# Interfaces.net
KiCad netlist of a schematic drawn in Altium Designer
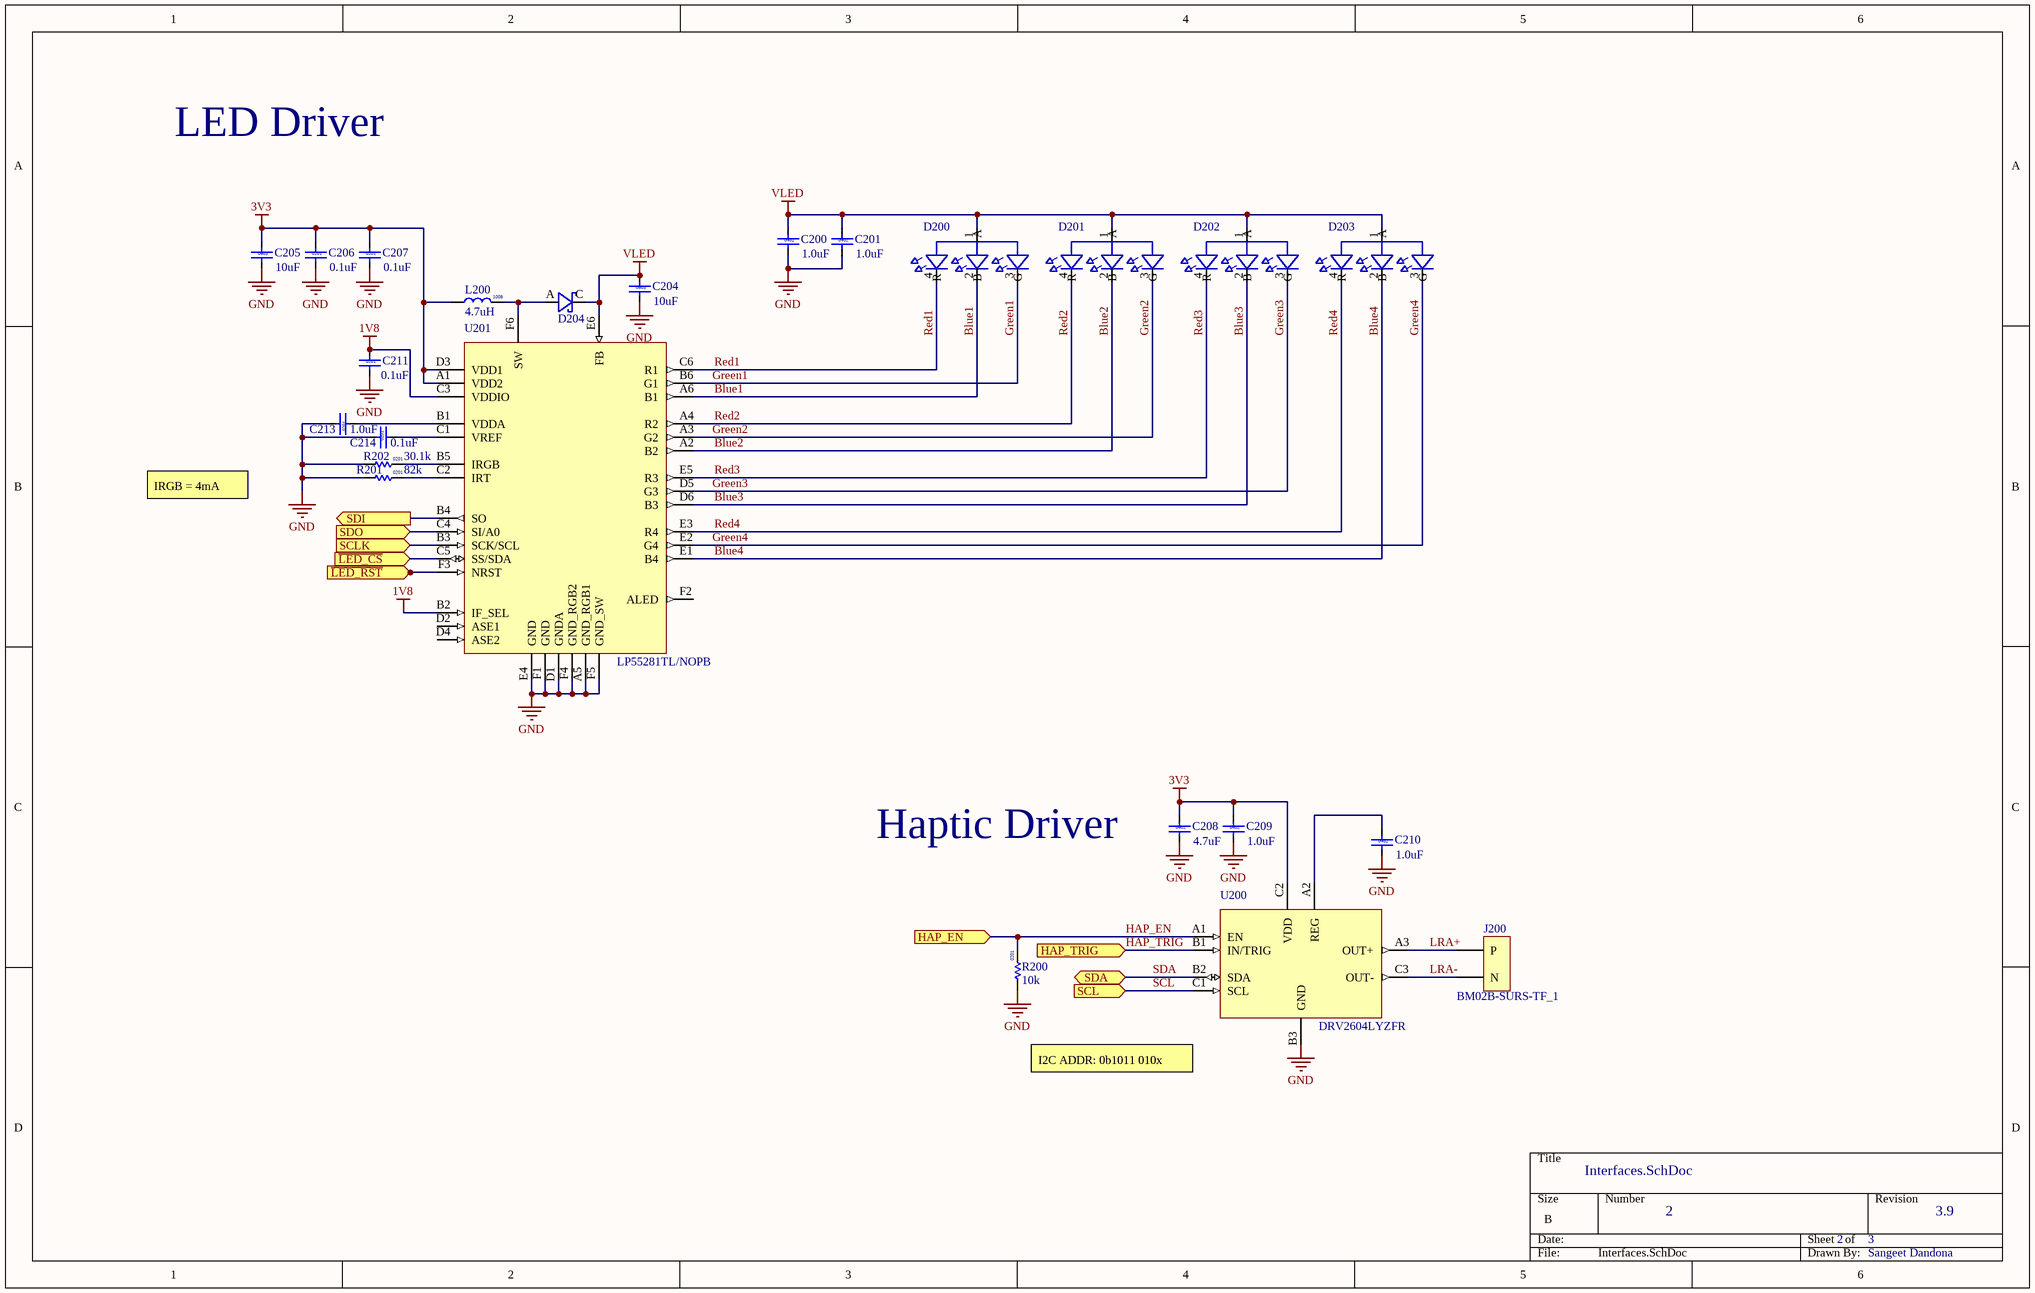
[diagram p0: Interfaces.SchDoc]

(export (version "E")
  (design (tool "Eeschema 10.0.6"))
  (components
    (comp (ref "C200")
      (value "1.0uF")
      (footprint "Cap 0402 HD")
      (description "CAP CER 1UF 10V 10% X5R 0402")
      (fields (field (name "SIZE") "0402") (field (name "MF") "Murata Electronics North America"))
      (libsource (lib "Rigado_AltiumLib") (part "Cap Chip"))
    )
    (comp (ref "C201")
      (value "1.0uF")
      (footprint "Cap 0402 HD")
      (description "CAP CER 1UF 10V 10% X5R 0402")
      (fields (field (name "SIZE") "0402") (field (name "MF") "Murata Electronics North America"))
      (libsource (lib "Rigado_AltiumLib") (part "Cap Chip"))
    )
    (comp (ref "C204")
      (value "10uF")
      (footprint "Cap 0603")
      (description "CAP CER 10UF 10V 20% X5R 0603")
      (fields (field (name "SIZE") "0603") (field (name "MF") "TDK Corporation"))
      (libsource (lib "Rigado_AltiumLib") (part "Cap Chip"))
    )
    (comp (ref "C205")
      (value "10uF")
      (footprint "Cap 0603")
      (description "CAP CER 10UF 10V 20% X5R 0603")
      (fields (field (name "SIZE") "0603") (field (name "MF") "TDK Corporation"))
      (libsource (lib "Rigado_AltiumLib") (part "Cap Chip"))
    )
    (comp (ref "C206")
      (value "0.1uF")
      (footprint "Cap 0201 HD")
      (description "CAP CER 0.1UF 6.3V 10% X5R 0201")
      (fields (field (name "SIZE") "0201") (field (name "MF") "Murata Electronics North America"))
      (libsource (lib "Rigado_AltiumLib") (part "Cap Chip"))
    )
    (comp (ref "C207")
      (value "0.1uF")
      (footprint "Cap 0201 HD")
      (description "CAP CER 0.1UF 6.3V 10% X5R 0201")
      (fields (field (name "SIZE") "0201") (field (name "MF") "Murata Electronics North America"))
      (libsource (lib "Rigado_AltiumLib") (part "Cap Chip"))
    )
    (comp (ref "C208")
      (value "4.7uF")
      (footprint "Cap 0402 HD")
      (description "CAP CER 4.7UF 10V 20% X5R 0402")
      (fields (field (name "SIZE") "0402") (field (name "MF") "Samsung Electro-Mechanics America, Inc."))
      (libsource (lib "Rigado_AltiumLib") (part "Cap Chip"))
    )
    (comp (ref "C209")
      (value "1.0uF")
      (footprint "Cap 0402 HD")
      (description "CAP CER 1UF 10V 10% X5R 0402")
      (fields (field (name "SIZE") "0402") (field (name "MF") "Murata Electronics North America"))
      (libsource (lib "Rigado_AltiumLib") (part "Cap Chip"))
    )
    (comp (ref "C210")
      (value "1.0uF")
      (footprint "Cap 0402 HD")
      (description "CAP CER 1UF 10V 10% X5R 0402")
      (fields (field (name "SIZE") "0402") (field (name "MF") "Murata Electronics North America"))
      (libsource (lib "Rigado_AltiumLib") (part "Cap Chip"))
    )
    (comp (ref "C211")
      (value "0.1uF")
      (footprint "Cap 0201 HD")
      (description "CAP CER 0.1UF 6.3V 10% X5R 0201")
      (fields (field (name "SIZE") "0201") (field (name "MF") "Murata Electronics North America"))
      (libsource (lib "Rigado_AltiumLib") (part "Cap Chip"))
    )
    (comp (ref "C213")
      (value "1.0uF")
      (footprint "Cap 0201 HD")
      (description "CAP CER 1UF 6.3V 20% X5R 0201")
      (fields (field (name "SIZE") "0201") (field (name "MF") "Samsung Electro-Mechanics America, Inc."))
      (libsource (lib "Rigado_AltiumLib") (part "Cap Chip"))
    )
    (comp (ref "C214")
      (value "0.1uF")
      (footprint "Cap 0201 HD")
      (description "CAP CER 0.1UF 6.3V 10% X5R 0201")
      (fields (field (name "SIZE") "0201") (field (name "MF") "Murata Electronics North America"))
      (libsource (lib "Rigado_AltiumLib") (part "Cap Chip"))
    )
    (comp (ref "D200")
      (value "~")
      (footprint "4-PLCC")
      (description "LED RGB 3-IN-1 SMD 4PLCC")
      (fields (field (name "MF") "Cree Inc."))
      (libsource (lib "Rigado_AltiumLib") (part "LED_RGB_CA_2"))
    )
    (comp (ref "D201")
      (value "~")
      (footprint "4-PLCC")
      (description "LED RGB 3-IN-1 SMD 4PLCC")
      (fields (field (name "MF") "Cree Inc."))
      (libsource (lib "Rigado_AltiumLib") (part "LED_RGB_CA_2"))
    )
    (comp (ref "D202")
      (value "~")
      (footprint "4-PLCC")
      (description "LED RGB 3-IN-1 SMD 4PLCC")
      (fields (field (name "MF") "Cree Inc."))
      (libsource (lib "Rigado_AltiumLib") (part "LED_RGB_CA_2"))
    )
    (comp (ref "D203")
      (value "~")
      (footprint "4-PLCC")
      (description "LED RGB 3-IN-1 SMD 4PLCC")
      (fields (field (name "MF") "Cree Inc."))
      (libsource (lib "Rigado_AltiumLib") (part "LED_RGB_CA_2"))
    )
    (comp (ref "D204")
      (value "~")
      (footprint "SOD-123F_U")
      (description "DIODE SCHOTTKY 20V 1A SOD123FL")
      (fields (field (name "MF") "ON Semiconductor"))
      (libsource (lib "LOCAL_Rigado_AltiumLib") (part "Diode_Schottky"))
    )
    (comp (ref "J200")
      (value "BM02B-SURS-TF_1")
      (footprint "BM02B-SURS-TF")
      (description "CONN HDR SUR TOP 2POS 0.8MM TIN")
      (fields (field (name "MF") "JST Sales America Inc."))
      (libsource (lib "JWB-001_Main") (part "BM02B-SURS-TF_1"))
    )
    (comp (ref "L200")
      (value "4.7uH")
      (footprint "IND 1008")
      (description "FIXED IND 4.7UH 1A 250 MOHM SMD")
      (fields (field (name "SIZE") "1008") (field (name "MF") "Samsung Electro-Mechanics America, Inc."))
      (libsource (lib "Rigado_AltiumLib") (part "Ind sm"))
    )
    (comp (ref "R200")
      (value "10k")
      (footprint "RES 0201 HD")
      (description "RES SMD 10K OHM 5% 1/20W 0201")
      (fields (field (name "SIZE") "0201") (field (name "MF") "Rohm Semiconductor"))
      (libsource (lib "Rigado_AltiumLib") (part "Res sm"))
    )
    (comp (ref "R201")
      (value "82k")
      (footprint "RES 0201 HD")
      (description "RES SMD 82K OHM 1% 1/20W 0201")
      (fields (field (name "SIZE") "0201") (field (name "MF") "Samsung Electro-Mechanics America, Inc."))
      (libsource (lib "Rigado_AltiumLib") (part "Res sm"))
    )
    (comp (ref "R202")
      (value "30.1k")
      (footprint "RES 0201 HD")
      (description "RES SMD 30.1K OHM 1% 1/20W 0201")
      (fields (field (name "SIZE") "0201") (field (name "MF") "Yageo"))
      (libsource (lib "Rigado_AltiumLib") (part "Res sm"))
    )
    (comp (ref "U200")
      (value "~")
      (footprint "BGA0.5P3x3-9Pin")
      (description "IC ERM/LRA HAPTIC DRIVER 9DSBGA")
      (fields (field (name "MF") "Texas Instruments") (field (name "MFPN") "DRV2604LYZFR"))
      (libsource (lib "Rigado_AltiumLib") (part "DRV2604L"))
    )
    (comp (ref "U201")
      (value "~")
      (footprint "BGA0.5P6x6-36Pin")
      (description "IC LED DRIVER RGLTR DIM 36USMD")
      (fields (field (name "MF") "Texas Instruments") (field (name "MFPN") "LP55281TL/NOPB"))
      (libsource (lib "Rigado_AltiumLib") (part "LP55281"))
    )
  )
  (nets
    (net (code "1") (name "/Blue1") (class "Default")
      (node (ref "D200") (pin "2") (pinfunction "B_2") (pintype "passive"))
      (node (ref "U201") (pin "A6") (pinfunction "B1_A6") (pintype "output"))
    )
    (net (code "2") (name "/Blue2") (class "Default")
      (node (ref "D201") (pin "2") (pinfunction "B_2") (pintype "passive"))
      (node (ref "U201") (pin "A2") (pinfunction "B2_A2") (pintype "output"))
    )
    (net (code "3") (name "/Blue3") (class "Default")
      (node (ref "D202") (pin "2") (pinfunction "B_2") (pintype "passive"))
      (node (ref "U201") (pin "D6") (pinfunction "B3_D6") (pintype "output"))
    )
    (net (code "4") (name "/Blue4") (class "Default")
      (node (ref "D203") (pin "2") (pinfunction "B_2") (pintype "passive"))
      (node (ref "U201") (pin "E1") (pinfunction "B4_E1") (pintype "output"))
    )
    (net (code "5") (name "/Green1") (class "Default")
      (node (ref "D200") (pin "3") (pinfunction "G_3") (pintype "passive"))
      (node (ref "U201") (pin "B6") (pinfunction "G1_B6") (pintype "output"))
    )
    (net (code "6") (name "/Green2") (class "Default")
      (node (ref "D201") (pin "3") (pinfunction "G_3") (pintype "passive"))
      (node (ref "U201") (pin "A3") (pinfunction "G2_A3") (pintype "output"))
    )
    (net (code "7") (name "/Green3") (class "Default")
      (node (ref "D202") (pin "3") (pinfunction "G_3") (pintype "passive"))
      (node (ref "U201") (pin "D5") (pinfunction "G3_D5") (pintype "output"))
    )
    (net (code "8") (name "/Green4") (class "Default")
      (node (ref "D203") (pin "3") (pinfunction "G_3") (pintype "passive"))
      (node (ref "U201") (pin "E2") (pinfunction "G4_E2") (pintype "output"))
    )
    (net (code "9") (name "/HAP_EN") (class "Default")
      (node (ref "R200") (pin "2") (pinfunction "2_2") (pintype "passive"))
      (node (ref "U200") (pin "A1") (pinfunction "EN_A1") (pintype "input"))
    )
    (net (code "10") (name "/HAP_TRIG") (class "Default")
      (node (ref "U200") (pin "B1") (pinfunction "IN/TRIG_B1") (pintype "input"))
    )
    (net (code "11") (name "/LED_CS") (class "Default")
      (node (ref "U201") (pin "C5") (pinfunction "SS/SDA_C5") (pintype "bidirectional"))
    )
    (net (code "12") (name "/LED_RST") (class "Default")
      (node (ref "U201") (pin "F3") (pinfunction "NRST_F3") (pintype "input"))
    )
    (net (code "13") (name "/LRA+") (class "Default")
      (node (ref "J200") (pin "1") (pinfunction "P_1") (pintype "passive"))
      (node (ref "U200") (pin "A3") (pinfunction "OUT+_A3") (pintype "output"))
    )
    (net (code "14") (name "/LRA-") (class "Default")
      (node (ref "J200") (pin "2") (pinfunction "N_2") (pintype "passive"))
      (node (ref "U200") (pin "C3") (pinfunction "OUT-_C3") (pintype "output"))
    )
    (net (code "15") (name "/Red1") (class "Default")
      (node (ref "D200") (pin "4") (pinfunction "R_4") (pintype "passive"))
      (node (ref "U201") (pin "C6") (pinfunction "R1_C6") (pintype "output"))
    )
    (net (code "16") (name "/Red2") (class "Default")
      (node (ref "D201") (pin "4") (pinfunction "R_4") (pintype "passive"))
      (node (ref "U201") (pin "A4") (pinfunction "R2_A4") (pintype "output"))
    )
    (net (code "17") (name "/Red3") (class "Default")
      (node (ref "D202") (pin "4") (pinfunction "R_4") (pintype "passive"))
      (node (ref "U201") (pin "E5") (pinfunction "R3_E5") (pintype "output"))
    )
    (net (code "18") (name "/Red4") (class "Default")
      (node (ref "D203") (pin "4") (pinfunction "R_4") (pintype "passive"))
      (node (ref "U201") (pin "E3") (pinfunction "R4_E3") (pintype "output"))
    )
    (net (code "19") (name "/SCL") (class "Default")
      (node (ref "U200") (pin "C1") (pinfunction "SCL_C1") (pintype "input"))
    )
    (net (code "20") (name "/SCLK") (class "Default")
      (node (ref "U201") (pin "B3") (pinfunction "SCK/SCL_B3") (pintype "input"))
    )
    (net (code "21") (name "/SDA") (class "Default")
      (node (ref "U200") (pin "B2") (pinfunction "SDA_B2") (pintype "bidirectional"))
    )
    (net (code "22") (name "/SDI") (class "Default")
      (node (ref "U201") (pin "B4") (pinfunction "SO_B4") (pintype "output"))
    )
    (net (code "23") (name "/SDO") (class "Default")
      (node (ref "U201") (pin "C4") (pinfunction "SI/A0_C4") (pintype "input"))
    )
    (net (code "24") (name "1V8") (class "Default")
      (node (ref "C211") (pin "1") (pinfunction "1_1") (pintype "passive"))
      (node (ref "U201") (pin "B2") (pinfunction "IF_SEL_B2") (pintype "input"))
      (node (ref "U201") (pin "C3") (pinfunction "VDDIO_C3") (pintype "power_in"))
    )
    (net (code "25") (name "3V3") (class "Default")
      (node (ref "C205") (pin "1") (pinfunction "1_1") (pintype "passive"))
      (node (ref "C206") (pin "1") (pinfunction "1_1") (pintype "passive"))
      (node (ref "C207") (pin "1") (pinfunction "1_1") (pintype "passive"))
      (node (ref "C208") (pin "1") (pinfunction "1_1") (pintype "passive"))
      (node (ref "C209") (pin "1") (pinfunction "1_1") (pintype "passive"))
      (node (ref "L200") (pin "1") (pinfunction "1_1") (pintype "passive"))
      (node (ref "U200") (pin "C2") (pinfunction "VDD_C2") (pintype "power_in"))
      (node (ref "U201") (pin "A1") (pinfunction "VDD2_A1") (pintype "power_in"))
      (node (ref "U201") (pin "D3") (pinfunction "VDD1_D3") (pintype "power_in"))
    )
    (net (code "26") (name "GND") (class "Default")
      (node (ref "C200") (pin "2") (pinfunction "2_2") (pintype "passive"))
      (node (ref "C201") (pin "2") (pinfunction "2_2") (pintype "passive"))
      (node (ref "C204") (pin "2") (pinfunction "2_2") (pintype "passive"))
      (node (ref "C205") (pin "2") (pinfunction "2_2") (pintype "passive"))
      (node (ref "C206") (pin "2") (pinfunction "2_2") (pintype "passive"))
      (node (ref "C207") (pin "2") (pinfunction "2_2") (pintype "passive"))
      (node (ref "C208") (pin "2") (pinfunction "2_2") (pintype "passive"))
      (node (ref "C209") (pin "2") (pinfunction "2_2") (pintype "passive"))
      (node (ref "C210") (pin "2") (pinfunction "2_2") (pintype "passive"))
      (node (ref "C211") (pin "2") (pinfunction "2_2") (pintype "passive"))
      (node (ref "C213") (pin "2") (pinfunction "2_2") (pintype "passive"))
      (node (ref "C214") (pin "1") (pinfunction "1_1") (pintype "passive"))
      (node (ref "R200") (pin "1") (pinfunction "1_1") (pintype "passive"))
      (node (ref "R201") (pin "1") (pinfunction "1_1") (pintype "passive"))
      (node (ref "R202") (pin "1") (pinfunction "1_1") (pintype "passive"))
      (node (ref "U200") (pin "B3") (pinfunction "GND_B3") (pintype "power_in"))
      (node (ref "U201") (pin "A5") (pinfunction "GND_RGB1_A5") (pintype "power_in"))
      (node (ref "U201") (pin "D1") (pinfunction "GNDA_D1") (pintype "power_in"))
      (node (ref "U201") (pin "E4") (pinfunction "GND_E4") (pintype "power_in"))
      (node (ref "U201") (pin "F1") (pinfunction "GND_F1") (pintype "power_in"))
      (node (ref "U201") (pin "F4") (pinfunction "GND_RGB2_F4") (pintype "power_in"))
      (node (ref "U201") (pin "F5") (pinfunction "GND_SW_F5") (pintype "power_in"))
    )
    (net (code "27") (name "Net-(U200-REG)") (class "Default")
      (node (ref "C210") (pin "1") (pinfunction "1_1") (pintype "passive"))
      (node (ref "U200") (pin "A2") (pinfunction "REG_A2") (pintype "power_in"))
    )
    (net (code "28") (name "Net-(U201-IRGB)") (class "Default")
      (node (ref "R202") (pin "2") (pinfunction "2_2") (pintype "passive"))
      (node (ref "U201") (pin "B5") (pinfunction "IRGB_B5") (pintype "passive"))
    )
    (net (code "29") (name "Net-(U201-IRT)") (class "Default")
      (node (ref "R201") (pin "2") (pinfunction "2_2") (pintype "passive"))
      (node (ref "U201") (pin "C2") (pinfunction "IRT_C2") (pintype "passive"))
    )
    (net (code "30") (name "Net-(U201-SW)") (class "Default")
      (node (ref "D204") (pin "A") (pintype "passive"))
      (node (ref "L200") (pin "2") (pinfunction "2_2") (pintype "passive"))
      (node (ref "U201") (pin "F6") (pinfunction "SW_F6") (pintype "power_in"))
    )
    (net (code "31") (name "Net-(U201-VDDA)") (class "Default")
      (node (ref "C213") (pin "1") (pinfunction "1_1") (pintype "passive"))
      (node (ref "U201") (pin "B1") (pinfunction "VDDA_B1") (pintype "power_in"))
    )
    (net (code "32") (name "Net-(U201-VREF)") (class "Default")
      (node (ref "C214") (pin "2") (pinfunction "2_2") (pintype "passive"))
      (node (ref "U201") (pin "C1") (pinfunction "VREF_C1") (pintype "passive"))
    )
    (net (code "33") (name "VLED") (class "Default")
      (node (ref "C200") (pin "1") (pinfunction "1_1") (pintype "passive"))
      (node (ref "C201") (pin "1") (pinfunction "1_1") (pintype "passive"))
      (node (ref "C204") (pin "1") (pinfunction "1_1") (pintype "passive"))
      (node (ref "D200") (pin "1") (pinfunction "A_1") (pintype "passive"))
      (node (ref "D201") (pin "1") (pinfunction "A_1") (pintype "passive"))
      (node (ref "D202") (pin "1") (pinfunction "A_1") (pintype "passive"))
      (node (ref "D203") (pin "1") (pinfunction "A_1") (pintype "passive"))
      (node (ref "D204") (pin "C") (pintype "passive"))
      (node (ref "U201") (pin "E6") (pinfunction "FB_E6") (pintype "input"))
    )
    (net (code "34") (name "unconnected-(U201-ALED-PadF2)") (class "Default")
      (node (ref "U201") (pin "F2") (pinfunction "ALED_F2") (pintype "output"))
    )
    (net (code "35") (name "unconnected-(U201-ASE1-PadD2)") (class "Default")
      (node (ref "U201") (pin "D2") (pinfunction "ASE1_D2") (pintype "input"))
    )
    (net (code "36") (name "unconnected-(U201-ASE2-PadD4)") (class "Default")
      (node (ref "U201") (pin "D4") (pinfunction "ASE2_D4") (pintype "input"))
    )
  )
)
